# Face_You_Like.net
KiCad netlist of a schematic drawn in EAGLE
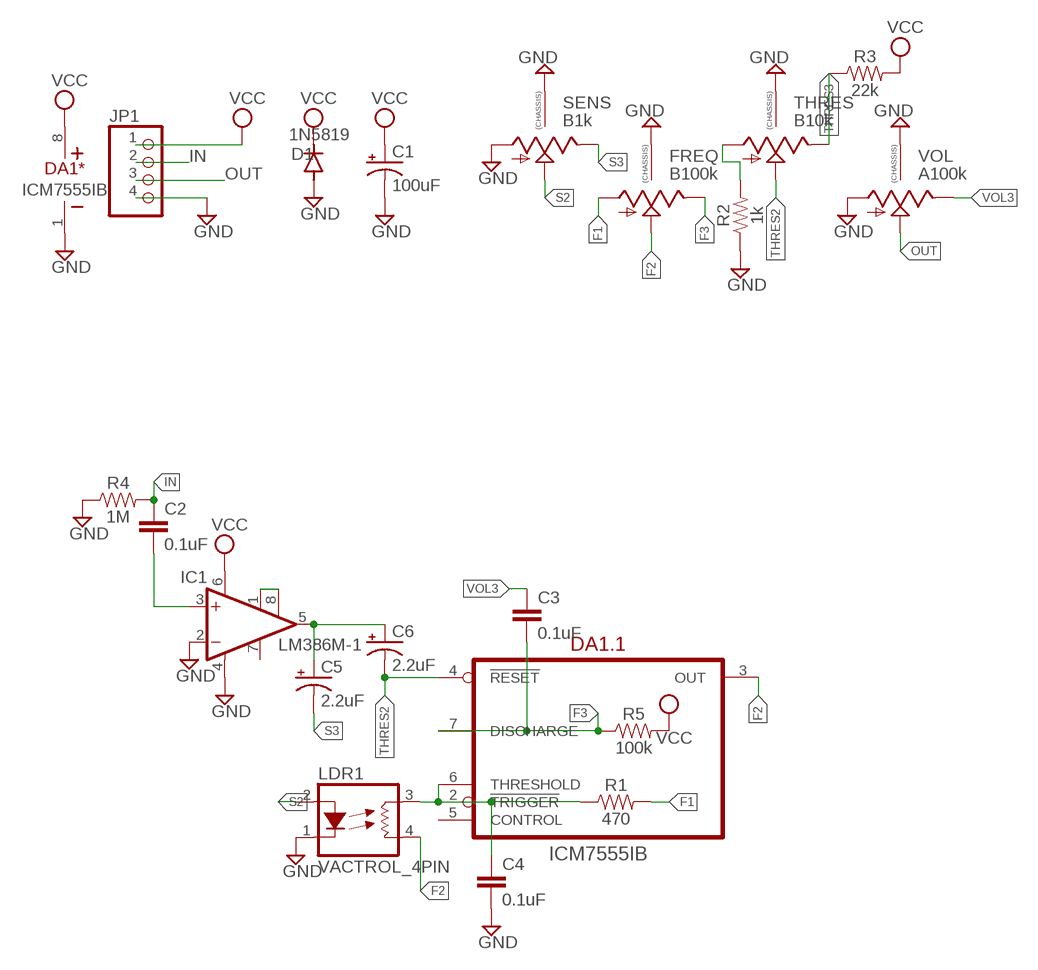
[diagram p0: schematic, sheet 1]

(export (version "E")
  (design (tool "Eeschema 10.0.6"))
  (components
    (comp (ref "C1")
      (value "100uF")
      (footprint "eagle-import:PAN_B_SMD+THRU")
      (libsource (lib "eagle-import") (part "CAP_SMD+THRUPAN_B"))
    )
    (comp (ref "C2")
      (value "0.1uF")
      (footprint "eagle-import:0603")
      (libsource (lib "eagle-import") (part "0.1UF-0603-25V-(+80/-20%)"))
    )
    (comp (ref "C3")
      (value "0.1uF")
      (footprint "eagle-import:0603")
      (libsource (lib "eagle-import") (part "0.1UF-0603-25V-(+80/-20%)"))
    )
    (comp (ref "C4")
      (value "0.1uF")
      (footprint "eagle-import:0603")
      (libsource (lib "eagle-import") (part "0.1UF-0603-25V-(+80/-20%)"))
    )
    (comp (ref "C5")
      (value "2.2uF")
      (footprint "eagle-import:PAN_B_SMD+THRU")
      (libsource (lib "eagle-import") (part "CAP_SMD+THRUPAN_B"))
    )
    (comp (ref "C6")
      (value "2.2uF")
      (footprint "eagle-import:PAN_B_SMD+THRU")
      (libsource (lib "eagle-import") (part "CAP_SMD+THRUPAN_B"))
    )
    (comp (ref "D1")
      (value "1N5819")
      (footprint "eagle-import:SOD123")
      (libsource (lib "eagle-import") (part "DIODE-SOD123"))
    )
    (comp (ref "DA1")
      (value "ICM7555IB")
      (footprint "eagle-import:SO-8")
      (libsource (lib "eagle-import") (part "ICM7555?IB"))
    )
    (comp (ref "FREQ")
      (value "B100k")
      (footprint "eagle-import:9MM_SNAP-IN_POT")
      (libsource (lib "eagle-import") (part "9MM_SNAP-IN_POT_CHASSIS"))
    )
    (comp (ref "IC1")
      (value "LM386M-1")
      (footprint "eagle-import:SO08")
      (libsource (lib "eagle-import") (part "LM386?-M1"))
    )
    (comp (ref "JP1")
      (value "PINHD-1X4")
      (footprint "eagle-import:1X04")
      (libsource (lib "eagle-import") (part "PINHD-1X4"))
    )
    (comp (ref "LDR1")
      (value "VACTROL_4PIN")
      (footprint "eagle-import:VACTROL_4PIN_VTL5C")
      (libsource (lib "eagle-import") (part "VACTROL_4PIN"))
    )
    (comp (ref "R1")
      (value "470")
      (footprint "eagle-import:0603")
      (libsource (lib "eagle-import") (part "470OHM-0603-1/10W-1%"))
    )
    (comp (ref "R2")
      (value "1k")
      (footprint "eagle-import:0603")
      (libsource (lib "eagle-import") (part "1KOHM-0603-1/10W-1%"))
    )
    (comp (ref "R3")
      (value "22k")
      (footprint "eagle-import:0603")
      (libsource (lib "eagle-import") (part "22KOHM-0603-1/10W-1%"))
    )
    (comp (ref "R4")
      (value "1M")
      (footprint "eagle-import:0603")
      (libsource (lib "eagle-import") (part "1MOHM-0603-1/4W-5%"))
    )
    (comp (ref "R5")
      (value "100k")
      (footprint "eagle-import:0603")
      (libsource (lib "eagle-import") (part "100KOHM-0603-1/10W-1%"))
    )
    (comp (ref "SENS")
      (value "B1k")
      (footprint "eagle-import:9MM_SNAP-IN_POT")
      (libsource (lib "eagle-import") (part "9MM_SNAP-IN_POT_CHASSIS"))
    )
    (comp (ref "THRES")
      (value "B10k")
      (footprint "eagle-import:9MM_SNAP-IN_POT")
      (libsource (lib "eagle-import") (part "9MM_SNAP-IN_POT_CHASSIS"))
    )
    (comp (ref "VOL")
      (value "A100k")
      (footprint "eagle-import:9MM_SNAP-IN_POT")
      (libsource (lib "eagle-import") (part "9MM_SNAP-IN_POT_CHASSIS"))
    )
  )
  (nets
    (net (code "1") (name "F1") (class "Default")
      (node (ref "FREQ") (pin "1") (pinfunction "A_1") (pintype "passive"))
      (node (ref "R1") (pin "2") (pinfunction "2_2") (pintype "passive"))
    )
    (net (code "2") (name "F2") (class "Default")
      (node (ref "DA1") (pin "3") (pinfunction "OUT_3") (pintype "bidirectional"))
      (node (ref "FREQ") (pin "2") (pinfunction "S_2") (pintype "passive"))
      (node (ref "LDR1") (pin "4") (pinfunction "RES2_4") (pintype "passive"))
    )
    (net (code "3") (name "F3") (class "Default")
      (node (ref "C3") (pin "2") (pinfunction "2_2") (pintype "passive"))
      (node (ref "DA1") (pin "7") (pinfunction "DISCHARGE_7") (pintype "bidirectional"))
      (node (ref "FREQ") (pin "3") (pinfunction "E_3") (pintype "passive"))
      (node (ref "R5") (pin "1") (pinfunction "1_1") (pintype "passive"))
    )
    (net (code "4") (name "GND") (class "Default")
      (node (ref "C1") (pin "-") (pinfunction "-_-") (pintype "passive"))
      (node (ref "C1") (pin "--") (pinfunction "-_--") (pintype "passive"))
      (node (ref "C4") (pin "2") (pinfunction "2_2") (pintype "passive"))
      (node (ref "D1") (pin "A") (pinfunction "A_A") (pintype "passive"))
      (node (ref "DA1") (pin "1") (pinfunction "V-_1") (pintype "power_in"))
      (node (ref "FREQ") (pin "CHASSIS1") (pinfunction "P$1_CHASSIS1") (pintype "passive"))
      (node (ref "FREQ") (pin "CHASSIS2") (pinfunction "P$1_CHASSIS2") (pintype "passive"))
      (node (ref "IC1") (pin "2") (pinfunction "-IN_2") (pintype "input"))
      (node (ref "IC1") (pin "4") (pinfunction "GND_4") (pintype "power_in"))
      (node (ref "JP1") (pin "4") (pinfunction "4_4") (pintype "passive"))
      (node (ref "LDR1") (pin "1") (pinfunction "LED-_1") (pintype "passive"))
      (node (ref "R2") (pin "1") (pinfunction "1_1") (pintype "passive"))
      (node (ref "R4") (pin "1") (pinfunction "1_1") (pintype "passive"))
      (node (ref "SENS") (pin "1") (pinfunction "A_1") (pintype "passive"))
      (node (ref "SENS") (pin "CHASSIS1") (pinfunction "P$1_CHASSIS1") (pintype "passive"))
      (node (ref "SENS") (pin "CHASSIS2") (pinfunction "P$1_CHASSIS2") (pintype "passive"))
      (node (ref "THRES") (pin "CHASSIS1") (pinfunction "P$1_CHASSIS1") (pintype "passive"))
      (node (ref "THRES") (pin "CHASSIS2") (pinfunction "P$1_CHASSIS2") (pintype "passive"))
      (node (ref "VOL") (pin "1") (pinfunction "A_1") (pintype "passive"))
      (node (ref "VOL") (pin "CHASSIS1") (pinfunction "P$1_CHASSIS1") (pintype "passive"))
      (node (ref "VOL") (pin "CHASSIS2") (pinfunction "P$1_CHASSIS2") (pintype "passive"))
    )
    (net (code "5") (name "IN") (class "Default")
      (node (ref "C2") (pin "1") (pinfunction "1_1") (pintype "passive"))
      (node (ref "JP1") (pin "2") (pinfunction "2_2") (pintype "passive"))
      (node (ref "R4") (pin "2") (pinfunction "2_2") (pintype "passive"))
    )
    (net (code "6") (name "Net-(DA1B-THRESHOLD)") (class "Default")
      (node (ref "C4") (pin "1") (pinfunction "1_1") (pintype "passive"))
      (node (ref "DA1") (pin "2") (pinfunction "~{TRIGGER}_2") (pintype "bidirectional"))
      (node (ref "DA1") (pin "6") (pinfunction "THRESHOLD_6") (pintype "bidirectional"))
      (node (ref "LDR1") (pin "3") (pinfunction "RES1_3") (pintype "passive"))
      (node (ref "R1") (pin "1") (pinfunction "1_1") (pintype "passive"))
    )
    (net (code "7") (name "Net-(IC1-+IN)") (class "Default")
      (node (ref "C2") (pin "2") (pinfunction "2_2") (pintype "passive"))
      (node (ref "IC1") (pin "3") (pinfunction "+IN_3") (pintype "input"))
    )
    (net (code "8") (name "Net-(IC1-GAIN-Pad1)") (class "Default")
      (node (ref "IC1") (pin "1") (pinfunction "GAIN_1") (pintype "passive"))
      (node (ref "IC1") (pin "8") (pinfunction "GAIN_8") (pintype "passive"))
    )
    (net (code "9") (name "Net-(IC1-OUT)") (class "Default")
      (node (ref "C5") (pin "+") (pinfunction "+_+") (pintype "passive"))
      (node (ref "C5") (pin "++") (pinfunction "+_++") (pintype "passive"))
      (node (ref "C6") (pin "+") (pinfunction "+_+") (pintype "passive"))
      (node (ref "C6") (pin "++") (pinfunction "+_++") (pintype "passive"))
      (node (ref "IC1") (pin "5") (pinfunction "OUT_5") (pintype "output"))
    )
    (net (code "10") (name "Net-(THRES-A)") (class "Default")
      (node (ref "R2") (pin "2") (pinfunction "2_2") (pintype "passive"))
      (node (ref "THRES") (pin "1") (pinfunction "A_1") (pintype "passive"))
    )
    (net (code "11") (name "OUT") (class "Default")
      (node (ref "JP1") (pin "3") (pinfunction "3_3") (pintype "passive"))
      (node (ref "VOL") (pin "2") (pinfunction "S_2") (pintype "passive"))
    )
    (net (code "12") (name "S2") (class "Default")
      (node (ref "LDR1") (pin "2") (pinfunction "LED+_2") (pintype "passive"))
      (node (ref "SENS") (pin "2") (pinfunction "S_2") (pintype "passive"))
    )
    (net (code "13") (name "S3") (class "Default")
      (node (ref "C5") (pin "-") (pinfunction "-_-") (pintype "passive"))
      (node (ref "C5") (pin "--") (pinfunction "-_--") (pintype "passive"))
      (node (ref "SENS") (pin "3") (pinfunction "E_3") (pintype "passive"))
    )
    (net (code "14") (name "THRES2") (class "Default")
      (node (ref "C6") (pin "-") (pinfunction "-_-") (pintype "passive"))
      (node (ref "C6") (pin "--") (pinfunction "-_--") (pintype "passive"))
      (node (ref "DA1") (pin "4") (pinfunction "~{RESET}_4") (pintype "input"))
      (node (ref "THRES") (pin "2") (pinfunction "S_2") (pintype "passive"))
    )
    (net (code "15") (name "THRES3") (class "Default")
      (node (ref "R3") (pin "1") (pinfunction "1_1") (pintype "passive"))
      (node (ref "THRES") (pin "3") (pinfunction "E_3") (pintype "passive"))
    )
    (net (code "16") (name "VCC") (class "Default")
      (node (ref "C1") (pin "+") (pinfunction "+_+") (pintype "passive"))
      (node (ref "C1") (pin "++") (pinfunction "+_++") (pintype "passive"))
      (node (ref "D1") (pin "C") (pinfunction "C_C") (pintype "passive"))
      (node (ref "DA1") (pin "8") (pinfunction "V+_8") (pintype "power_in"))
      (node (ref "IC1") (pin "6") (pinfunction "VS_6") (pintype "power_in"))
      (node (ref "JP1") (pin "1") (pinfunction "1_1") (pintype "passive"))
      (node (ref "R3") (pin "2") (pinfunction "2_2") (pintype "passive"))
      (node (ref "R5") (pin "2") (pinfunction "2_2") (pintype "passive"))
    )
    (net (code "17") (name "VOL3") (class "Default")
      (node (ref "C3") (pin "1") (pinfunction "1_1") (pintype "passive"))
      (node (ref "VOL") (pin "3") (pinfunction "E_3") (pintype "passive"))
    )
    (net (code "18") (name "unconnected-(DA1B-CONTROL-Pad5)") (class "Default")
      (node (ref "DA1") (pin "5") (pinfunction "CONTROL_5") (pintype "bidirectional"))
    )
    (net (code "19") (name "unconnected-(IC1-BYPASS-Pad7)") (class "Default")
      (node (ref "IC1") (pin "7") (pinfunction "BYPASS_7") (pintype "passive"))
    )
  )
)
